# DC-DC_v2.net
KiCad netlist of a schematic drawn in EAGLE
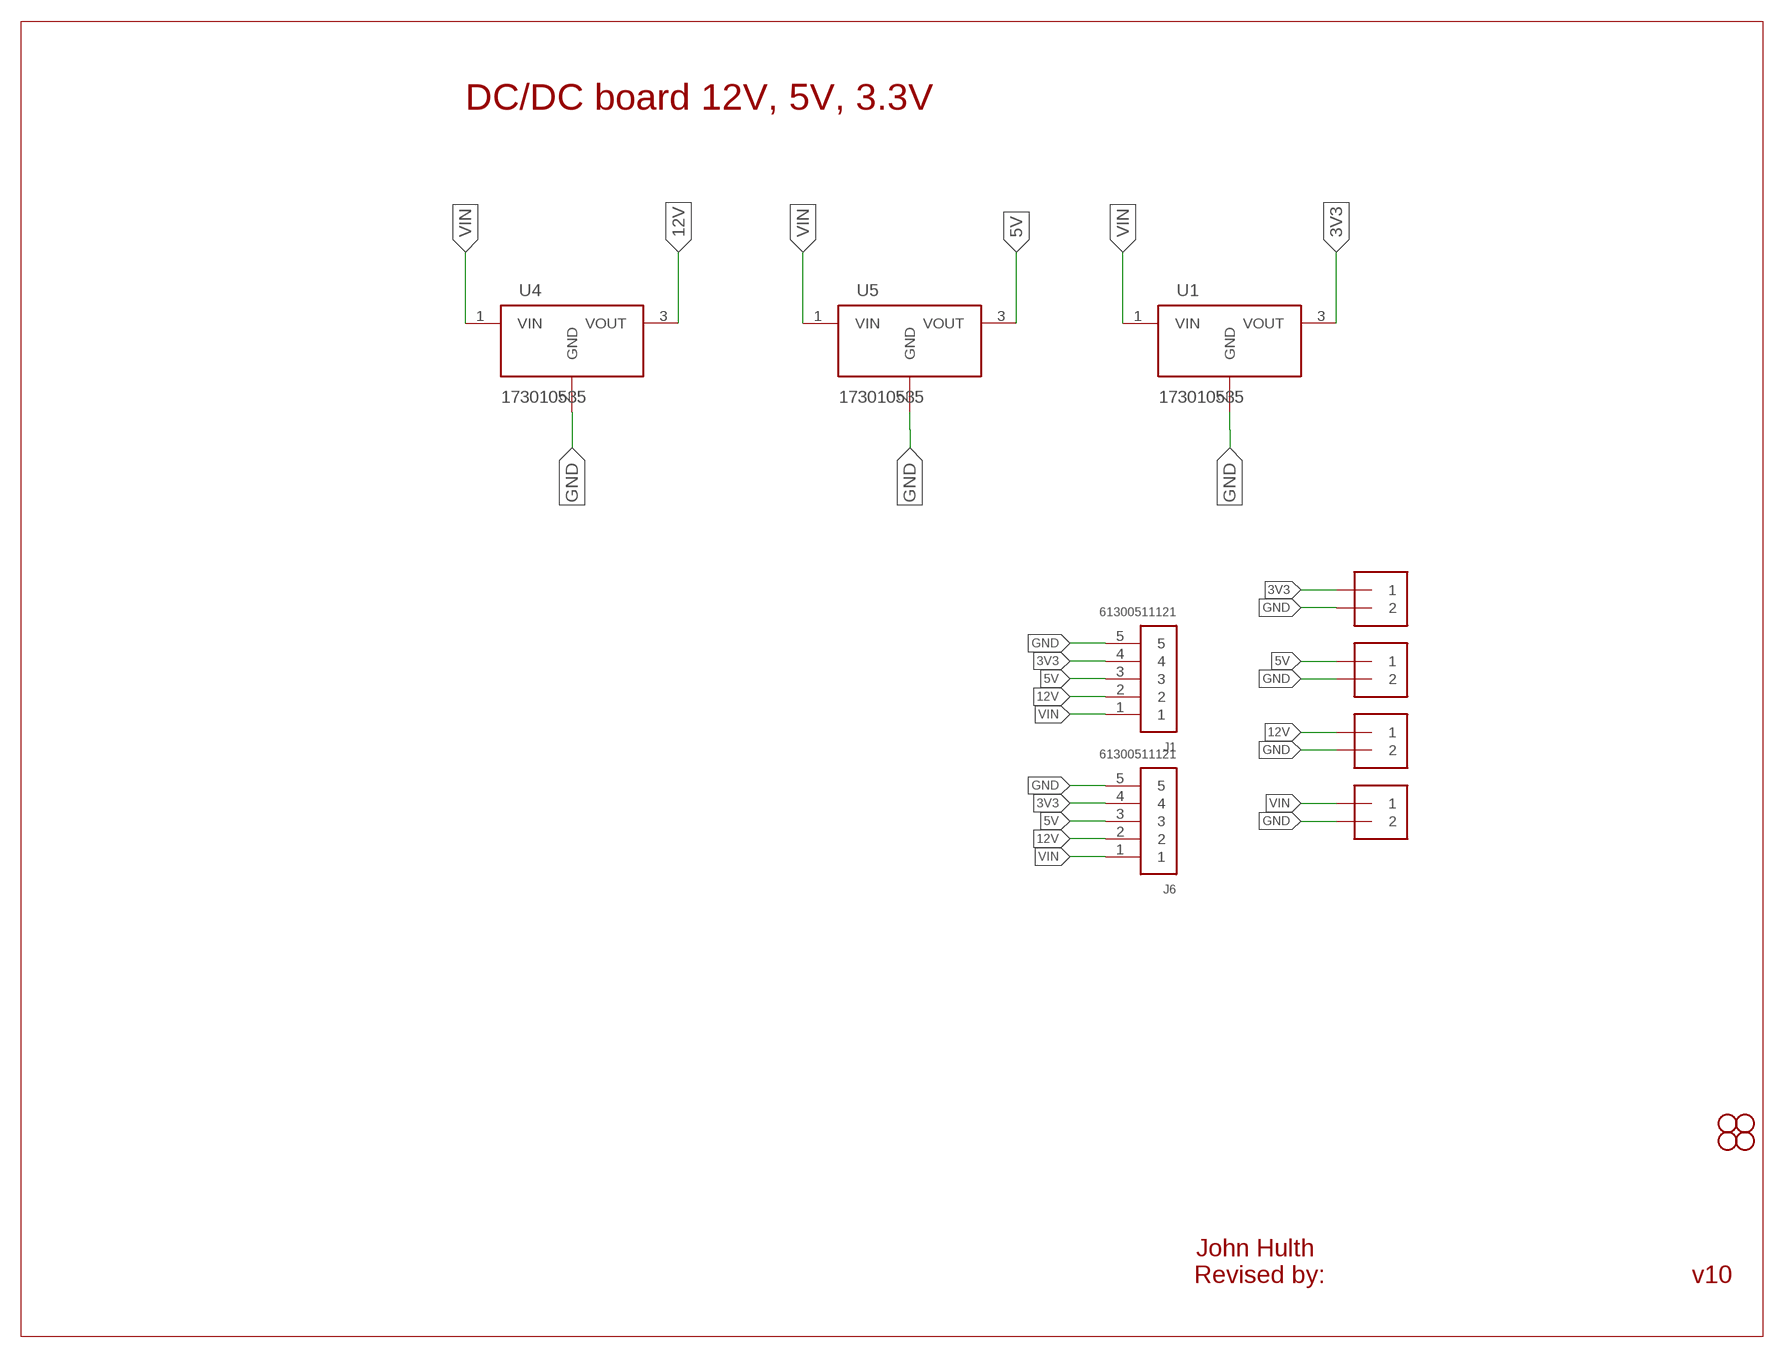
[diagram p0: schematic, sheet 1]

(export (version "E")
  (design (tool "Eeschema 10.0.6"))
  (components
    (comp (ref "J1")
      (value "61300511121")
      (footprint "eagle-import:61300511121")
      (fields
        (field (name "DIGI_KEY_PART_NUMBER") "732-5318-ND")
        (field (name "MANUFACTURER") "Wurth Electronics Inc.")
        (field (name "CREATED_BY") "PCBLayout.com")
      )
      (libsource (lib "eagle-import") (part "61300511121"))
    )
    (comp (ref "J2")
      (value "1X2-3.5MM")
      (footprint "eagle-import:1X2-3.5MM")
      (libsource (lib "eagle-import") (part "1X2-3.5MM"))
    )
    (comp (ref "J3")
      (value "1X2-3.5MM")
      (footprint "eagle-import:1X2-3.5MM")
      (libsource (lib "eagle-import") (part "1X2-3.5MM"))
    )
    (comp (ref "J4")
      (value "1X2-3.5MM")
      (footprint "eagle-import:1X2-3.5MM")
      (libsource (lib "eagle-import") (part "1X2-3.5MM"))
    )
    (comp (ref "J5")
      (value "1X2-3.5MM")
      (footprint "eagle-import:1X2-3.5MM")
      (libsource (lib "eagle-import") (part "1X2-3.5MM"))
    )
    (comp (ref "J6")
      (value "61300511121")
      (footprint "eagle-import:61300511121")
      (fields
        (field (name "DIGI_KEY_PART_NUMBER") "732-5318-ND")
        (field (name "MANUFACTURER") "Wurth Electronics Inc.")
        (field (name "CREATED_BY") "PCBLayout.com")
      )
      (libsource (lib "eagle-import") (part "61300511121"))
    )
    (comp (ref "JP2")
      (value "STAND-OFF")
      (footprint "eagle-import:STAND-OFF")
      (libsource (lib "eagle-import") (part "STAND-OFF"))
    )
    (comp (ref "JP3")
      (value "STAND-OFF")
      (footprint "eagle-import:STAND-OFF")
      (libsource (lib "eagle-import") (part "STAND-OFF"))
    )
    (comp (ref "JP8")
      (value "STAND-OFF")
      (footprint "eagle-import:STAND-OFF")
      (libsource (lib "eagle-import") (part "STAND-OFF"))
    )
    (comp (ref "JP9")
      (value "STAND-OFF")
      (footprint "eagle-import:STAND-OFF")
      (libsource (lib "eagle-import") (part "STAND-OFF"))
    )
    (comp (ref "U1")
      (value "173010535")
      (footprint "eagle-import:173010535")
      (fields
        (field (name "DIGIKEY_PARTNO") "732-173010535-ND")
        (field (name "MANUFACTURER") "Würth Elektronik")
        (field (name "CREATED_BY") "PCBLayout.com")
      )
      (libsource (lib "eagle-import") (part "173010535"))
    )
    (comp (ref "U4")
      (value "173010535")
      (footprint "eagle-import:173010535")
      (fields
        (field (name "DIGIKEY_PARTNO") "732-173010535-ND")
        (field (name "MANUFACTURER") "Würth Elektronik")
        (field (name "CREATED_BY") "PCBLayout.com")
      )
      (libsource (lib "eagle-import") (part "173010535"))
    )
    (comp (ref "U5")
      (value "173010535")
      (footprint "eagle-import:173010535")
      (fields
        (field (name "DIGIKEY_PARTNO") "732-173010535-ND")
        (field (name "MANUFACTURER") "Würth Elektronik")
        (field (name "CREATED_BY") "PCBLayout.com")
      )
      (libsource (lib "eagle-import") (part "173010535"))
    )
  )
  (nets
    (net (code "1") (name "3V3") (class "Default")
      (node (ref "J1") (pin "4") (pinfunction "4_4") (pintype "passive"))
      (node (ref "J2") (pin "1") (pinfunction "1_1") (pintype "passive"))
      (node (ref "J6") (pin "4") (pinfunction "4_4") (pintype "passive"))
      (node (ref "U1") (pin "3") (pinfunction "VOUT_3") (pintype "power_in"))
    )
    (net (code "2") (name "5V") (class "Default")
      (node (ref "J1") (pin "3") (pinfunction "3_3") (pintype "passive"))
      (node (ref "J3") (pin "1") (pinfunction "1_1") (pintype "passive"))
      (node (ref "J6") (pin "3") (pinfunction "3_3") (pintype "passive"))
      (node (ref "U5") (pin "3") (pinfunction "VOUT_3") (pintype "power_in"))
    )
    (net (code "3") (name "12V") (class "Default")
      (node (ref "J1") (pin "2") (pinfunction "2_2") (pintype "passive"))
      (node (ref "J4") (pin "1") (pinfunction "1_1") (pintype "passive"))
      (node (ref "J6") (pin "2") (pinfunction "2_2") (pintype "passive"))
      (node (ref "U4") (pin "3") (pinfunction "VOUT_3") (pintype "power_in"))
    )
    (net (code "4") (name "GND") (class "Default")
      (node (ref "J1") (pin "5") (pinfunction "5_5") (pintype "passive"))
      (node (ref "J2") (pin "2") (pinfunction "2_2") (pintype "passive"))
      (node (ref "J3") (pin "2") (pinfunction "2_2") (pintype "passive"))
      (node (ref "J4") (pin "2") (pinfunction "2_2") (pintype "passive"))
      (node (ref "J5") (pin "2") (pinfunction "2_2") (pintype "passive"))
      (node (ref "J6") (pin "5") (pinfunction "5_5") (pintype "passive"))
      (node (ref "U1") (pin "2") (pinfunction "GND_2") (pintype "power_in"))
      (node (ref "U4") (pin "2") (pinfunction "GND_2") (pintype "power_in"))
      (node (ref "U5") (pin "2") (pinfunction "GND_2") (pintype "power_in"))
    )
    (net (code "5") (name "VIN") (class "Default")
      (node (ref "J1") (pin "1") (pinfunction "1_1") (pintype "passive"))
      (node (ref "J5") (pin "1") (pinfunction "1_1") (pintype "passive"))
      (node (ref "J6") (pin "1") (pinfunction "1_1") (pintype "passive"))
      (node (ref "U1") (pin "1") (pinfunction "VIN_1") (pintype "power_in"))
      (node (ref "U4") (pin "1") (pinfunction "VIN_1") (pintype "power_in"))
      (node (ref "U5") (pin "1") (pinfunction "VIN_1") (pintype "power_in"))
    )
  )
)
